# External_ADC.net
KiCad netlist of a schematic drawn in Altium Designer
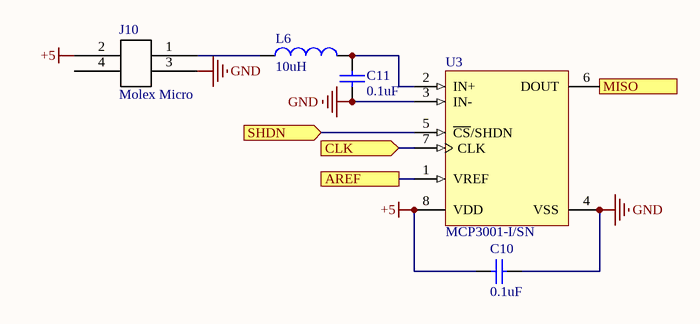
[diagram p0: External ADC.SchDoc]

(export (version "E")
  (design (tool "Eeschema 10.0.6"))
  (components
    (comp (ref "C10")
      (value "0.1uF")
      (footprint "CAPC2013X94X50LL20T25")
      (description "Chip Capacitor, 0.1 uF, +/- 5%, 50 V, -55 to 125 degC, 0805 (2012 Metric), RoHS, Tape and Reel")
      (fields (field (name "TOLERANCE") "5%") (field (name "MANUFACTURER") "AVX"))
      (libsource (lib "Altium Content Vault") (part "CAP-NP-2"))
    )
    (comp (ref "C11")
      (value "0.1uF")
      (footprint "CAPC2013X94X50LL20T25")
      (description "Chip Capacitor, 0.1 uF, +/- 5%, 50 V, -55 to 125 degC, 0805 (2012 Metric), RoHS, Tape and Reel")
      (fields (field (name "TOLERANCE") "5%") (field (name "MANUFACTURER") "AVX"))
      (libsource (lib "Altium Content Vault") (part "CAP-NP-2"))
    )
    (comp (ref "J10")
      (value "Molex Micro")
      (footprint "0430450427")
      (description "Molex micro-fit 3.0, P/N 0430450427")
      (libsource (lib "Husky Robotics Standard Library 2019-2020") (part "Molex micro-fit 4-pin (dual row schematic)"))
    )
    (comp (ref "L6")
      (value "10uH")
      (footprint "TDK-IND0805-125_V")
      (description "Multilayer Inductor, 10 uH, ±20%, 300 mOhm, 50MHz, 0805(2012)")
      (fields (field (name "PARTNUMBER") "MLZ2012N100LT"))
      (libsource (lib "Altium Content Vault") (part "TDK-IND_INDUCTOR-2"))
    )
    (comp (ref "U3")
      (value "MCP3001-I/SN")
      (footprint "SOIC-SN8_M")
      (description "2.7V 10-Bit A/D Converter with SPI Serial Interface, 8-Pin SOIC 150mil, Industrial Temperature")
      (libsource (lib "Altium Content Vault") (part "CON-ADC-MCP3001-8"))
    )
  )
  (nets
    (net (code "1") (name "+5") (class "Default")
      (node (ref "C10") (pin "1") (pinfunction "1_1") (pintype "passive"))
      (node (ref "J10") (pin "2") (pintype "passive"))
      (node (ref "U3") (pin "8") (pinfunction "VDD_8") (pintype "power_in"))
    )
    (net (code "2") (name "/AREF") (class "Default")
      (node (ref "U3") (pin "1") (pinfunction "VREF_1") (pintype "input"))
    )
    (net (code "3") (name "/CLK") (class "Default")
      (node (ref "U3") (pin "7") (pinfunction "CLK_7") (pintype "input"))
    )
    (net (code "4") (name "/MISO") (class "Default")
      (node (ref "U3") (pin "6") (pinfunction "DOUT_6") (pintype "tri_state"))
    )
    (net (code "5") (name "/SHDN") (class "Default")
      (node (ref "U3") (pin "5") (pinfunction "~{CS}/SHDN_5") (pintype "input"))
    )
    (net (code "6") (name "GND") (class "Default")
      (node (ref "C10") (pin "2") (pinfunction "2_2") (pintype "passive"))
      (node (ref "C11") (pin "1") (pinfunction "1_1") (pintype "passive"))
      (node (ref "J10") (pin "3") (pintype "passive"))
      (node (ref "U3") (pin "3") (pinfunction "IN-_3") (pintype "input"))
      (node (ref "U3") (pin "4") (pinfunction "VSS_4") (pintype "power_in"))
    )
    (net (code "7") (name "Net-(J10-Pad1)") (class "Default")
      (node (ref "J10") (pin "1") (pintype "passive"))
      (node (ref "L6") (pin "1") (pinfunction "1_1") (pintype "passive"))
    )
    (net (code "8") (name "Net-(U3-IN+)") (class "Default")
      (node (ref "C11") (pin "2") (pinfunction "2_2") (pintype "passive"))
      (node (ref "L6") (pin "2") (pinfunction "2_2") (pintype "passive"))
      (node (ref "U3") (pin "2") (pinfunction "IN+_2") (pintype "input"))
    )
    (net (code "9") (name "unconnected-(J10-Pad4)") (class "Default")
      (node (ref "J10") (pin "4") (pintype "passive"))
    )
  )
)
